# coin20mm_-_switched.net
KiCad netlist of a schematic drawn in EAGLE
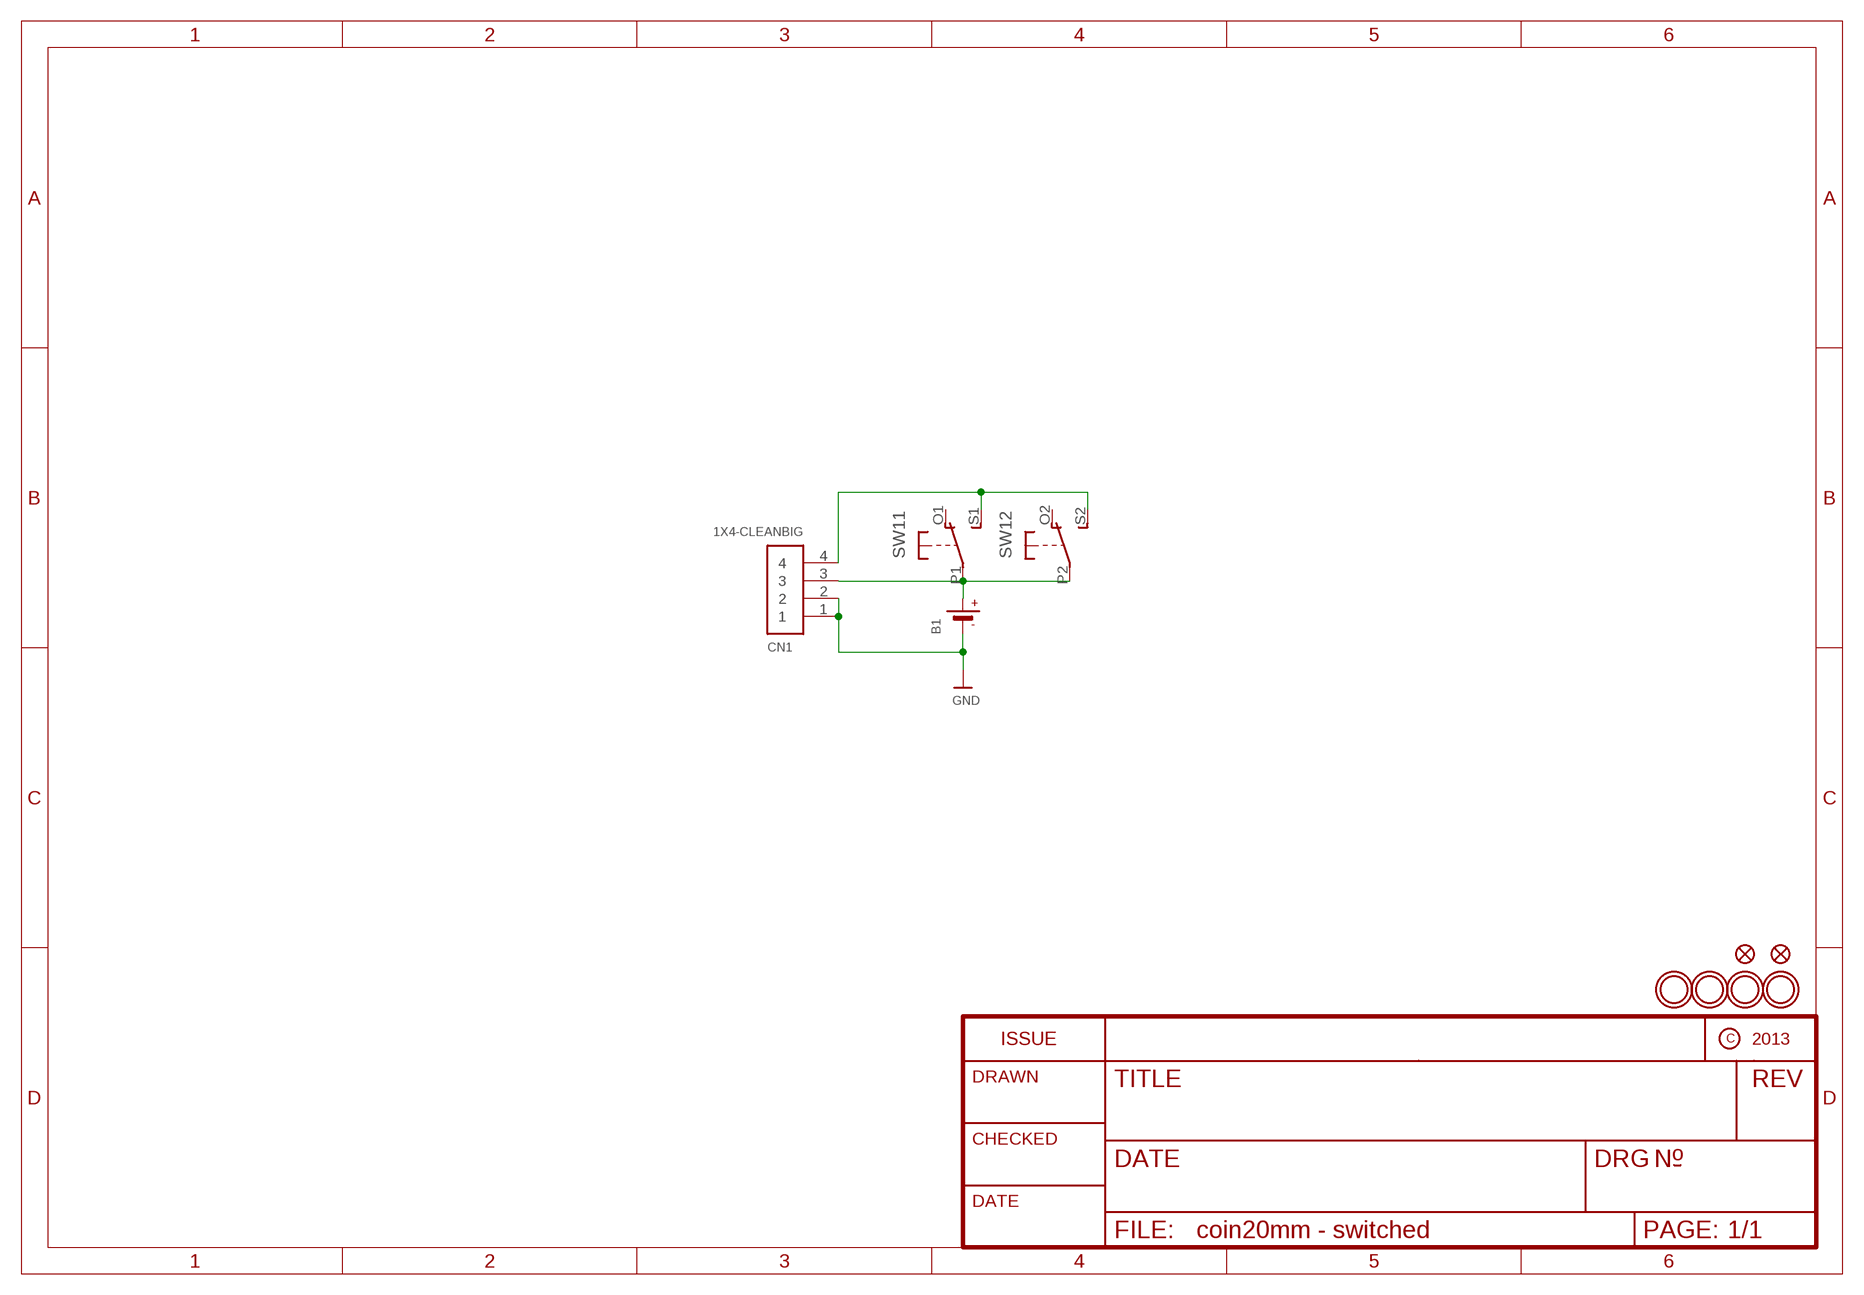
[diagram p0: schematic, sheet 1]

(export (version "E")
  (design (tool "Eeschema 10.0.6"))
  (components
    (comp (ref "B1")
      (value "BATTERYCR2032_BAT-HLD-001")
      (footprint "eagle-import:CR2032_SMT_BAT-HLD-001")
      (libsource (lib "eagle-import") (part "BATTERYCR2032_BAT-HLD-001"))
    )
    (comp (ref "CN1")
      (value "1X4-CLEANBIG")
      (footprint "eagle-import:1X04-CLEANBIG")
      (libsource (lib "eagle-import") (part "1X4-CLEANBIG"))
    )
    (comp (ref "FID1")
      (value "FIDUCIAL\"\"")
      (footprint "eagle-import:FIDUCIAL_1MM")
      (libsource (lib "eagle-import") (part "FIDUCIAL{dblquote}{dblquote}"))
    )
    (comp (ref "FID2")
      (value "FIDUCIAL\"\"")
      (footprint "eagle-import:FIDUCIAL_1MM")
      (libsource (lib "eagle-import") (part "FIDUCIAL{dblquote}{dblquote}"))
    )
    (comp (ref "SW1")
      (value "DPDT-EG1390")
      (footprint "eagle-import:EG1390")
      (libsource (lib "eagle-import") (part "DPDT-EG1390"))
    )
    (comp (ref "U$1")
      (value "MOUNTINGHOLE2.5")
      (footprint "eagle-import:MOUNTINGHOLE_2.5_PLATED")
      (libsource (lib "eagle-import") (part "MOUNTINGHOLE2.5"))
    )
    (comp (ref "U$2")
      (value "MOUNTINGHOLE2.5")
      (footprint "eagle-import:MOUNTINGHOLE_2.5_PLATED")
      (libsource (lib "eagle-import") (part "MOUNTINGHOLE2.5"))
    )
    (comp (ref "U$3")
      (value "MOUNTINGHOLE2.5")
      (footprint "eagle-import:MOUNTINGHOLE_2.5_PLATED")
      (libsource (lib "eagle-import") (part "MOUNTINGHOLE2.5"))
    )
    (comp (ref "U$5")
      (value "MOUNTINGHOLE2.5")
      (footprint "eagle-import:MOUNTINGHOLE_2.5_PLATED")
      (libsource (lib "eagle-import") (part "MOUNTINGHOLE2.5"))
    )
  )
  (nets
    (net (code "1") (name "GND") (class "Default")
      (node (ref "B1") (pin "-") (pinfunction "-_-") (pintype "passive"))
      (node (ref "CN1") (pin "1") (pinfunction "1_1") (pintype "bidirectional"))
      (node (ref "CN1") (pin "2") (pinfunction "2_2") (pintype "bidirectional"))
    )
    (net (code "2") (name "Net-(SW1A-P)") (class "Default")
      (node (ref "B1") (pin "+$1") (pinfunction "+_+$1") (pintype "passive"))
      (node (ref "B1") (pin "+$2") (pinfunction "+_+$2") (pintype "passive"))
      (node (ref "CN1") (pin "3") (pinfunction "3_3") (pintype "bidirectional"))
      (node (ref "SW1") (pin "P1") (pinfunction "P_P1") (pintype "passive"))
      (node (ref "SW1") (pin "P2") (pinfunction "P_P2") (pintype "passive"))
    )
    (net (code "3") (name "Net-(SW1A-S)") (class "Default")
      (node (ref "CN1") (pin "4") (pinfunction "4_4") (pintype "bidirectional"))
      (node (ref "SW1") (pin "S1") (pinfunction "S_S1") (pintype "passive"))
      (node (ref "SW1") (pin "S2") (pinfunction "S_S2") (pintype "passive"))
    )
    (net (code "4") (name "unconnected-(SW1A-O-PadO1)") (class "Default")
      (node (ref "SW1") (pin "O1") (pinfunction "O_O1") (pintype "passive"))
    )
    (net (code "5") (name "unconnected-(SW1B-O-PadO2)") (class "Default")
      (node (ref "SW1") (pin "O2") (pinfunction "O_O2") (pintype "passive"))
    )
  )
)
